# quadcopter.net
KiCad netlist of a schematic drawn in EAGLE
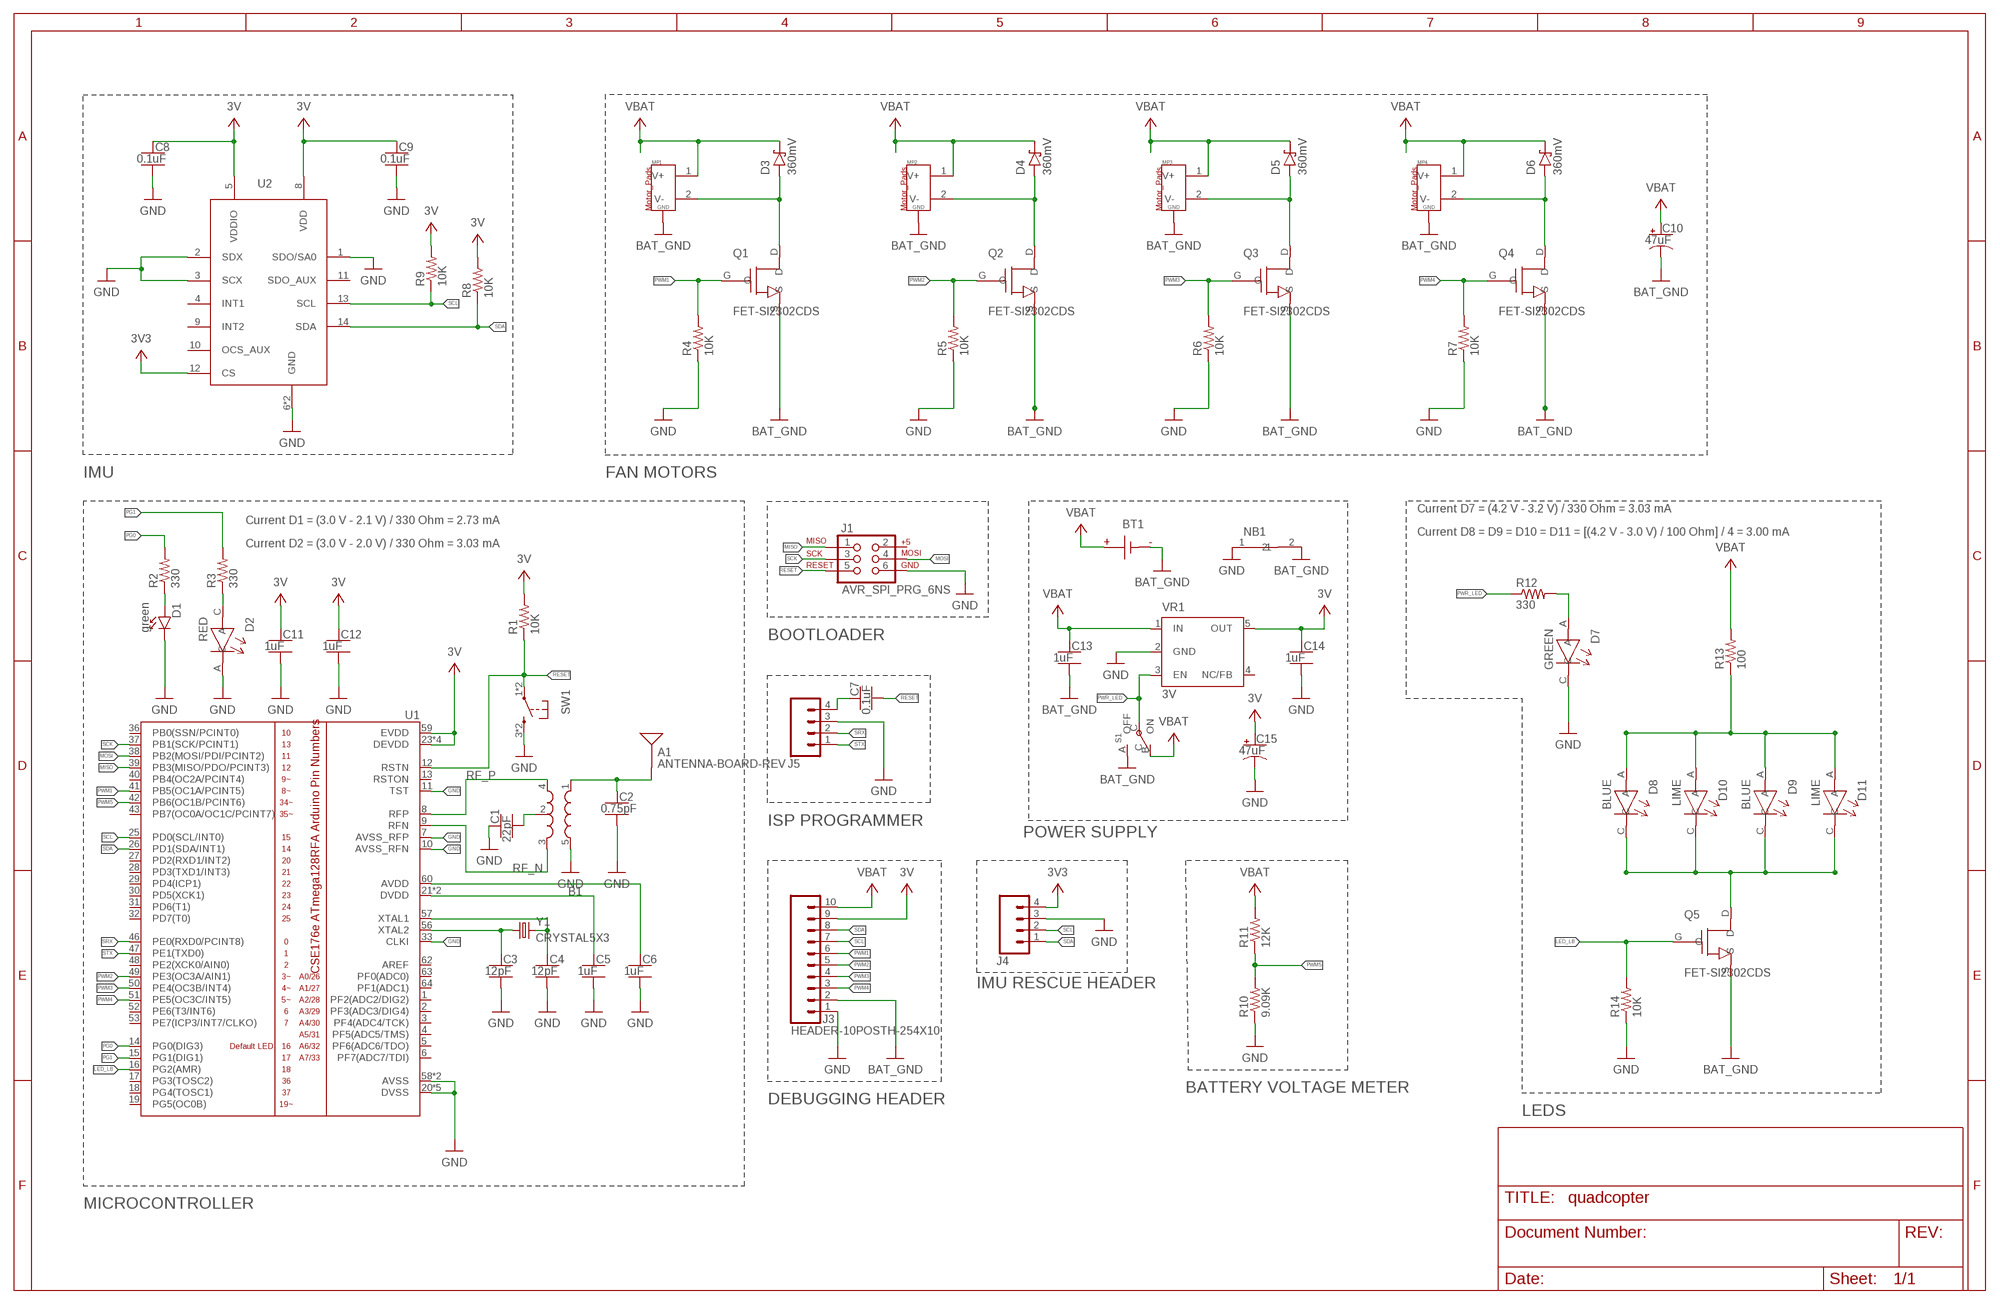
[diagram p0: schematic, sheet 1]

(export (version "E")
  (design (tool "Eeschema 10.0.6"))
  (components
    (comp (ref "A1")
      (value "ANTENNA-BOARD-REV")
      (footprint "eagle-import:ANT_PCB_2.4GHZ_NRF8001_1.6MM_1OZ_REV")
      (fields (field (name "MFR") "NA") (field (name "CREATOR") "Swanson"))
      (libsource (lib "eagle-import") (part "ANTENNA-BOARD-REV"))
    )
    (comp (ref "B1")
      (value "BALUN0805")
      (footprint "eagle-import:BALUN")
      (fields
        (field (name "MFR") "Wurth Electronics Inc.")
        (field (name "MPN") "748421245")
        (field (name "CREATOR") "Swanson")
        (field (name "REVIEWER") "Swanson")
      )
      (libsource (lib "eagle-import") (part "BALUN0805"))
    )
    (comp (ref "BT1")
      (value "BATTERY-SCREW-TERMINAL")
      (footprint "eagle-import:SCREW-TERMINAL-1X2-2.54MM")
      (fields (field (name "CREATOR") "Swanson"))
      (libsource (lib "eagle-import") (part "BATTERY-SCREW-TERMINAL"))
    )
    (comp (ref "C1")
      (value "22pF")
      (footprint "eagle-import:CAPC2012X140_HS")
      (fields
        (field (name "MFR") "Murata Electronics")
        (field (name "MPN") "GRM21A5C2E220JW01D")
        (field (name "CREATOR") "Swanson")
        (field (name "REVIEWER") "Swanson")
      )
      (libsource (lib "eagle-import") (part "CAPACITOR-NP_SMD-2012-0805_CERAMIC-22PF"))
    )
    (comp (ref "C2")
      (value "0.75pF")
      (footprint "eagle-import:CAPC2012X140_HS")
      (fields
        (field (name "MFR") "Murata Electronics")
        (field (name "MPN") "GQM2195C2AR75CB01D")
        (field (name "CREATOR") "Swanson")
        (field (name "REVIEWER") "Swanson")
      )
      (libsource (lib "eagle-import") (part "CAPACITOR-NP_SMD-2012-0805_CERAMIC-0.75PF"))
    )
    (comp (ref "C3")
      (value "12pF")
      (footprint "eagle-import:CAPC2012X140_HS")
      (fields
        (field (name "MFR") "Murata Electronics")
        (field (name "MPN") "GRM21A5C2E120JW01D")
        (field (name "CREATOR") "Swanson")
        (field (name "REVIEWER") "Swanson")
      )
      (libsource (lib "eagle-import") (part "CAPACITOR-NP_SMD-2012-0805_CERAMIC-12PF"))
    )
    (comp (ref "C4")
      (value "12pF")
      (footprint "eagle-import:CAPC2012X140_HS")
      (fields
        (field (name "MFR") "Murata Electronics")
        (field (name "MPN") "GRM21A5C2E120JW01D")
        (field (name "CREATOR") "Swanson")
        (field (name "REVIEWER") "Swanson")
      )
      (libsource (lib "eagle-import") (part "CAPACITOR-NP_SMD-2012-0805_CERAMIC-12PF"))
    )
    (comp (ref "C5")
      (value "1uF")
      (footprint "eagle-import:CAPC2012X140_HS")
      (fields
        (field (name "MFR") "Taiyo Yuden")
        (field (name "MPN") "TMK212B7105KG-T")
        (field (name "CREATOR") "Swanson")
        (field (name "REVIEWER") "Swanson")
      )
      (libsource (lib "eagle-import") (part "CAPACITOR-NP_SMD-2012-0805_CERAMIC-1UF"))
    )
    (comp (ref "C6")
      (value "1uF")
      (footprint "eagle-import:CAPC2012X140_HS")
      (fields
        (field (name "MFR") "Taiyo Yuden")
        (field (name "MPN") "TMK212B7105KG-T")
        (field (name "CREATOR") "Swanson")
        (field (name "REVIEWER") "Swanson")
      )
      (libsource (lib "eagle-import") (part "CAPACITOR-NP_SMD-2012-0805_CERAMIC-1UF"))
    )
    (comp (ref "C7")
      (value "0.1uF")
      (footprint "eagle-import:CAPC2012X140_HS")
      (fields
        (field (name "MFR") "TDK Corporation")
        (field (name "MPN") "C2012X7R2A104K125AA")
        (field (name "CREATOR") "Swanson")
        (field (name "REVIEWER") "Swanson")
      )
      (libsource (lib "eagle-import") (part "CAPACITOR-NP_SMD-2012-0805_CERAMIC-0.1UF"))
    )
    (comp (ref "C8")
      (value "0.1uF")
      (footprint "eagle-import:CAPC2012X140_HS")
      (fields
        (field (name "MFR") "TDK Corporation")
        (field (name "MPN") "C2012X7R2A104K125AA")
        (field (name "CREATOR") "Swanson")
        (field (name "REVIEWER") "Swanson")
      )
      (libsource (lib "eagle-import") (part "CAPACITOR-NP_SMD-2012-0805_CERAMIC-0.1UF"))
    )
    (comp (ref "C9")
      (value "0.1uF")
      (footprint "eagle-import:CAPC2012X140_HS")
      (fields
        (field (name "MFR") "TDK Corporation")
        (field (name "MPN") "C2012X7R2A104K125AA")
        (field (name "CREATOR") "Swanson")
        (field (name "REVIEWER") "Swanson")
      )
      (libsource (lib "eagle-import") (part "CAPACITOR-NP_SMD-2012-0805_CERAMIC-0.1UF"))
    )
    (comp (ref "C10")
      (value "47uF")
      (footprint "eagle-import:CAPMP3216X180")
      (fields
        (field (name "MFR") "AVX Corporation")
        (field (name "MPN") "TAJA476K006SNJV")
        (field (name "CREATOR") "Swanson")
      )
      (libsource (lib "eagle-import") (part "CAPACITOR-POL_47UF-SMD-1206-TAJA"))
    )
    (comp (ref "C11")
      (value "1uF")
      (footprint "eagle-import:CAPC2012X140_HS")
      (fields
        (field (name "MFR") "Taiyo Yuden")
        (field (name "MPN") "TMK212B7105KG-T")
        (field (name "CREATOR") "Swanson")
        (field (name "REVIEWER") "Swanson")
      )
      (libsource (lib "eagle-import") (part "CAPACITOR-NP_SMD-2012-0805_CERAMIC-1UF"))
    )
    (comp (ref "C12")
      (value "1uF")
      (footprint "eagle-import:CAPC2012X140_HS")
      (fields
        (field (name "MFR") "Taiyo Yuden")
        (field (name "MPN") "TMK212B7105KG-T")
        (field (name "CREATOR") "Swanson")
        (field (name "REVIEWER") "Swanson")
      )
      (libsource (lib "eagle-import") (part "CAPACITOR-NP_SMD-2012-0805_CERAMIC-1UF"))
    )
    (comp (ref "C13")
      (value "1uF")
      (footprint "eagle-import:CAPC2012X140_HS")
      (fields
        (field (name "MFR") "Taiyo Yuden")
        (field (name "MPN") "TMK212B7105KG-T")
        (field (name "CREATOR") "Swanson")
        (field (name "REVIEWER") "Swanson")
      )
      (libsource (lib "eagle-import") (part "CAPACITOR-NP_SMD-2012-0805_CERAMIC-1UF"))
    )
    (comp (ref "C14")
      (value "1uF")
      (footprint "eagle-import:CAPC2012X140_HS")
      (fields
        (field (name "MFR") "Taiyo Yuden")
        (field (name "MPN") "TMK212B7105KG-T")
        (field (name "CREATOR") "Swanson")
        (field (name "REVIEWER") "Swanson")
      )
      (libsource (lib "eagle-import") (part "CAPACITOR-NP_SMD-2012-0805_CERAMIC-1UF"))
    )
    (comp (ref "C15")
      (value "47uF")
      (footprint "eagle-import:CAPMP3216X180")
      (fields
        (field (name "MFR") "AVX Corporation")
        (field (name "MPN") "TAJA476K006SNJV")
        (field (name "CREATOR") "Swanson")
      )
      (libsource (lib "eagle-import") (part "CAPACITOR-POL_47UF-SMD-1206-TAJA"))
    )
    (comp (ref "D1")
      (value "green")
      (footprint "eagle-import:LEDSC125X200X120-2_HS")
      (fields
        (field (name "MFR") "Lite-On Inc")
        (field (name "MPN") "LTST-C170GKT")
        (field (name "CREATOR") "Swanson")
        (field (name "REVIEWER") "Swanson")
      )
      (libsource (lib "eagle-import") (part "DIODE-LED_SMD-2012-0805-GREEN"))
    )
    (comp (ref "D2")
      (value "RED")
      (footprint "eagle-import:0805_LED")
      (fields (field (name "CREATOR") "CHRISTOPHER VU"))
      (libsource (lib "eagle-import") (part "LED-RED"))
    )
    (comp (ref "D3")
      (value "360mV")
      (footprint "eagle-import:SODFL3516X96")
      (fields
        (field (name "MFR") "Toshiba Semiconductor and Storage")
        (field (name "MPN") "CRS08(TE85L,Q,M)")
        (field (name "CREATOR") "Swanson")
        (field (name "REVIEWER") "Swanson")
      )
      (libsource (lib "eagle-import") (part "DIODE-SCHOTTKY_-SMD-SOD123"))
    )
    (comp (ref "D4")
      (value "360mV")
      (footprint "eagle-import:SODFL3516X96")
      (fields
        (field (name "MFR") "Toshiba Semiconductor and Storage")
        (field (name "MPN") "CRS08(TE85L,Q,M)")
        (field (name "CREATOR") "Swanson")
        (field (name "REVIEWER") "Swanson")
      )
      (libsource (lib "eagle-import") (part "DIODE-SCHOTTKY_-SMD-SOD123"))
    )
    (comp (ref "D5")
      (value "360mV")
      (footprint "eagle-import:SODFL3516X96")
      (fields
        (field (name "MFR") "Toshiba Semiconductor and Storage")
        (field (name "MPN") "CRS08(TE85L,Q,M)")
        (field (name "CREATOR") "Swanson")
        (field (name "REVIEWER") "Swanson")
      )
      (libsource (lib "eagle-import") (part "DIODE-SCHOTTKY_-SMD-SOD123"))
    )
    (comp (ref "D6")
      (value "360mV")
      (footprint "eagle-import:SODFL3516X96")
      (fields
        (field (name "MFR") "Toshiba Semiconductor and Storage")
        (field (name "MPN") "CRS08(TE85L,Q,M)")
        (field (name "CREATOR") "Swanson")
        (field (name "REVIEWER") "Swanson")
      )
      (libsource (lib "eagle-import") (part "DIODE-SCHOTTKY_-SMD-SOD123"))
    )
    (comp (ref "D7")
      (value "GREEN")
      (footprint "eagle-import:0805_LED")
      (fields (field (name "CREATOR") "CHRISTOPHER VU"))
      (libsource (lib "eagle-import") (part "0805_LED-GREEN"))
    )
    (comp (ref "D8")
      (value "BLUE")
      (footprint "eagle-import:1411_LED")
      (fields (field (name "CREATOR") "CHRISTOPHER VU"))
      (libsource (lib "eagle-import") (part "1411_LED-BLUE"))
    )
    (comp (ref "D9")
      (value "BLUE")
      (footprint "eagle-import:1411_LED")
      (fields (field (name "CREATOR") "CHRISTOPHER VU"))
      (libsource (lib "eagle-import") (part "1411_LED-BLUE"))
    )
    (comp (ref "D10")
      (value "LIME")
      (footprint "eagle-import:1411_LED")
      (fields (field (name "CREATOR") "CHRISTOPHER VU"))
      (libsource (lib "eagle-import") (part "1411_LED-LIME"))
    )
    (comp (ref "D11")
      (value "LIME")
      (footprint "eagle-import:1411_LED")
      (fields (field (name "CREATOR") "CHRISTOPHER VU"))
      (libsource (lib "eagle-import") (part "1411_LED-LIME"))
    )
    (comp (ref "J1")
      (value "AVR_SPI_PRG_6NS")
      (footprint "eagle-import:2X3-NS")
      (fields
        (field (name "MFR") "Amphenol FCI")
        (field (name "MPN") "67997-206HLF")
        (field (name "CREATOR") "Swanson")
        (field (name "REVIEWER") "Swanson")
      )
      (libsource (lib "eagle-import") (part "AVR_SPI_PRG_6NS"))
    )
    (comp (ref "J3")
      (value "HEADER-10POSTH-254X10")
      (footprint "eagle-import:HDRV10W63P254_10X1_2540X254H838_HS")
      (fields
        (field (name "MFR") "Amphenol FCI")
        (field (name "MPN") "68000-110HLF")
        (field (name "CREATOR") "Swanson")
        (field (name "REVIEWER") "Swanson")
      )
      (libsource (lib "eagle-import") (part "HEADER-10POSTH-254X10"))
    )
    (comp (ref "J4")
      (value "HEADER-4POS-0.1IN-FEMALE")
      (footprint "eagle-import:HDRVR4W80P254_1X4_1066X254X850B")
      (fields (field (name "CREATOR") "Swanson"))
      (libsource (lib "eagle-import") (part "HEADER-4POS-0.1IN-FEMALE"))
    )
    (comp (ref "J5")
      (value "HEADER-4POS-0.1IN-FEMALE-SMD-BOTTOM-ENTRY")
      (footprint "eagle-import:HEADER-1X4-BOTTOM-ENTRY")
      (fields
        (field (name "MFR") "TE Connectivity AMP Connectors")
        (field (name "MPN") "1241152-4")
        (field (name "CREATOR") "Swanson")
      )
      (libsource (lib "eagle-import") (part "HEADER-4POS-0.1IN-FEMALE-SMD-BOTTOM-ENTRY"))
    )
    (comp (ref "MP1")
      (value "MOTOR_PADS_GND-MOLEX-SMD")
      (footprint "eagle-import:MOLEX-0532610271")
      (fields
        (field (name "MFR") "Molex")
        (field (name "MPN") "532610271")
        (field (name "CREATOR") "Swanson")
      )
      (libsource (lib "eagle-import") (part "MOTOR_PADS_GND-MOLEX-SMD"))
    )
    (comp (ref "MP2")
      (value "MOTOR_PADS_GND-MOLEX-SMD")
      (footprint "eagle-import:MOLEX-0532610271")
      (fields
        (field (name "MFR") "Molex")
        (field (name "MPN") "532610271")
        (field (name "CREATOR") "Swanson")
      )
      (libsource (lib "eagle-import") (part "MOTOR_PADS_GND-MOLEX-SMD"))
    )
    (comp (ref "MP3")
      (value "MOTOR_PADS_GND-MOLEX-SMD")
      (footprint "eagle-import:MOLEX-0532610271")
      (fields
        (field (name "MFR") "Molex")
        (field (name "MPN") "532610271")
        (field (name "CREATOR") "Swanson")
      )
      (libsource (lib "eagle-import") (part "MOTOR_PADS_GND-MOLEX-SMD"))
    )
    (comp (ref "MP4")
      (value "MOTOR_PADS_GND-MOLEX-SMD")
      (footprint "eagle-import:MOLEX-0532610271")
      (fields
        (field (name "MFR") "Molex")
        (field (name "MPN") "532610271")
        (field (name "CREATOR") "Swanson")
      )
      (libsource (lib "eagle-import") (part "MOTOR_PADS_GND-MOLEX-SMD"))
    )
    (comp (ref "NB1")
      (value "NET-BRIDGE")
      (footprint "eagle-import:NET-BRIDGE")
      (fields (field (name "CREATOR") "DARRYL TAYAG"))
      (libsource (lib "eagle-import") (part "NET-BRIDGE"))
    )
    (comp (ref "Q1")
      (value "FET-SI2302CDS")
      (footprint "eagle-import:SI2302MOSFET")
      (fields (field (name "CREATOR") "CHRISTOPHER VU"))
      (libsource (lib "eagle-import") (part "FET-SI2302CDS"))
    )
    (comp (ref "Q2")
      (value "FET-SI2302CDS")
      (footprint "eagle-import:SI2302MOSFET")
      (fields (field (name "CREATOR") "CHRISTOPHER VU"))
      (libsource (lib "eagle-import") (part "FET-SI2302CDS"))
    )
    (comp (ref "Q3")
      (value "FET-SI2302CDS")
      (footprint "eagle-import:SI2302MOSFET")
      (fields (field (name "CREATOR") "CHRISTOPHER VU"))
      (libsource (lib "eagle-import") (part "FET-SI2302CDS"))
    )
    (comp (ref "Q4")
      (value "FET-SI2302CDS")
      (footprint "eagle-import:SI2302MOSFET")
      (fields (field (name "CREATOR") "CHRISTOPHER VU"))
      (libsource (lib "eagle-import") (part "FET-SI2302CDS"))
    )
    (comp (ref "Q5")
      (value "FET-SI2302CDS")
      (footprint "eagle-import:SI2302MOSFET")
      (fields (field (name "CREATOR") "CHRISTOPHER VU"))
      (libsource (lib "eagle-import") (part "FET-SI2302CDS"))
    )
    (comp (ref "R1")
      (value "10K")
      (footprint "eagle-import:RESC2012X60_HS")
      (fields
        (field (name "MFR") "Yageo")
        (field (name "MPN") "RC0805JR-0710KL")
        (field (name "CREATOR") "Swanson")
        (field (name "REVIEWER") "Swanson")
      )
      (libsource (lib "eagle-import") (part "RESISTOR_SMD-2012-0805-10K"))
    )
    (comp (ref "R2")
      (value "330")
      (footprint "eagle-import:RESC2012X60_HS")
      (fields
        (field (name "MFR") "Yageo")
        (field (name "MPN") "RC0805JR-07330RL")
        (field (name "CREATOR") "Swanson")
        (field (name "REVIEWER") "Swanson")
      )
      (libsource (lib "eagle-import") (part "RESISTOR_SMD-2012-0805-330"))
    )
    (comp (ref "R3")
      (value "330")
      (footprint "eagle-import:RESC2012X60_HS")
      (fields
        (field (name "MFR") "Yageo")
        (field (name "MPN") "RC0805JR-07330RL")
        (field (name "CREATOR") "Swanson")
        (field (name "REVIEWER") "Swanson")
      )
      (libsource (lib "eagle-import") (part "RESISTOR_SMD-2012-0805-330"))
    )
    (comp (ref "R4")
      (value "10K")
      (footprint "eagle-import:RESC2012X60_HS")
      (fields
        (field (name "MFR") "Yageo")
        (field (name "MPN") "RC0805JR-0710KL")
        (field (name "CREATOR") "Swanson")
        (field (name "REVIEWER") "Swanson")
      )
      (libsource (lib "eagle-import") (part "RESISTOR_SMD-2012-0805-10K"))
    )
    (comp (ref "R5")
      (value "10K")
      (footprint "eagle-import:RESC2012X60_HS")
      (fields
        (field (name "MFR") "Yageo")
        (field (name "MPN") "RC0805JR-0710KL")
        (field (name "CREATOR") "Swanson")
        (field (name "REVIEWER") "Swanson")
      )
      (libsource (lib "eagle-import") (part "RESISTOR_SMD-2012-0805-10K"))
    )
    (comp (ref "R6")
      (value "10K")
      (footprint "eagle-import:RESC2012X60_HS")
      (fields
        (field (name "MFR") "Yageo")
        (field (name "MPN") "RC0805JR-0710KL")
        (field (name "CREATOR") "Swanson")
        (field (name "REVIEWER") "Swanson")
      )
      (libsource (lib "eagle-import") (part "RESISTOR_SMD-2012-0805-10K"))
    )
    (comp (ref "R7")
      (value "10K")
      (footprint "eagle-import:RESC2012X60_HS")
      (fields
        (field (name "MFR") "Yageo")
        (field (name "MPN") "RC0805JR-0710KL")
        (field (name "CREATOR") "Swanson")
        (field (name "REVIEWER") "Swanson")
      )
      (libsource (lib "eagle-import") (part "RESISTOR_SMD-2012-0805-10K"))
    )
    (comp (ref "R8")
      (value "10K")
      (footprint "eagle-import:RESC2012X60_HS")
      (fields
        (field (name "MFR") "Yageo")
        (field (name "MPN") "RC0805JR-0710KL")
        (field (name "CREATOR") "Swanson")
        (field (name "REVIEWER") "Swanson")
      )
      (libsource (lib "eagle-import") (part "RESISTOR_SMD-2012-0805-10K"))
    )
    (comp (ref "R9")
      (value "10K")
      (footprint "eagle-import:RESC2012X60_HS")
      (fields
        (field (name "MFR") "Yageo")
        (field (name "MPN") "RC0805JR-0710KL")
        (field (name "CREATOR") "Swanson")
        (field (name "REVIEWER") "Swanson")
      )
      (libsource (lib "eagle-import") (part "RESISTOR_SMD-2012-0805-10K"))
    )
    (comp (ref "R10")
      (value "9.09K")
      (footprint "eagle-import:RESC2012X60_HS")
      (fields (field (name "CREATOR") "Swanson"))
      (libsource (lib "eagle-import") (part "RESISTOR_SMD-2012-0805-9.09K"))
    )
    (comp (ref "R11")
      (value "12K")
      (footprint "eagle-import:RESC2012X60_HS")
      (fields (field (name "CREATOR") "Swanson"))
      (libsource (lib "eagle-import") (part "RESISTOR_SMD-2012-0805-12K"))
    )
    (comp (ref "R12")
      (value "330")
      (footprint "eagle-import:RESC2012X60_HS")
      (fields
        (field (name "MFR") "Yageo")
        (field (name "MPN") "RC0805JR-07330RL")
        (field (name "CREATOR") "Swanson")
        (field (name "REVIEWER") "Swanson")
      )
      (libsource (lib "eagle-import") (part "RESISTOR_SMD-2012-0805-330"))
    )
    (comp (ref "R13")
      (value "100")
      (footprint "eagle-import:RESC2012X60_HS")
      (fields
        (field (name "MFR") "Yageo")
        (field (name "MPN") "RC0805JR-07100RL")
        (field (name "CREATOR") "Swanson")
        (field (name "REVIEWER") "Swanson")
      )
      (libsource (lib "eagle-import") (part "RESISTOR_SMD-2012-0805-100"))
    )
    (comp (ref "R14")
      (value "10K")
      (footprint "eagle-import:RESC2012X60_HS")
      (fields
        (field (name "MFR") "Yageo")
        (field (name "MPN") "RC0805JR-0710KL")
        (field (name "CREATOR") "Swanson")
        (field (name "REVIEWER") "Swanson")
      )
      (libsource (lib "eagle-import") (part "RESISTOR_SMD-2012-0805-10K"))
    )
    (comp (ref "S1")
      (value "POWER-SWITCH-MFS201N-9-Z-SMD-EDGE")
      (footprint "eagle-import:JS102011SAQN")
      (fields
        (field (name "MFR") "C&K")
        (field (name "MPN") "JS102011SAQN")
        (field (name "CREATOR") "Swanson")
      )
      (libsource (lib "eagle-import") (part "POWER-SWITCH-MFS201N-9-Z-SMD-EDGE"))
    )
    (comp (ref "SW1")
      (value "PUSHBUTTON_SMD-VERTICAL-1")
      (footprint "eagle-import:TE_FSM8JSMA_HS")
      (fields
        (field (name "MFR") "TE Connectivity Alcoswitch Switches")
        (field (name "MPN") "FSM4JSMA")
        (field (name "CREATOR") "Swanson")
        (field (name "REVIEWER") "Swanson")
      )
      (libsource (lib "eagle-import") (part "PUSHBUTTON_SMD-VERTICAL-1"))
    )
    (comp (ref "U1")
      (value "ATMEGA128RFA1")
      (footprint "eagle-import:QFN-64")
      (fields
        (field (name "MFR") "Microchip Technology")
        (field (name "MPN") "ATMEGA128RFA1-ZU")
        (field (name "CREATOR") "Swanson")
        (field (name "REVIEWER") "Swanson")
      )
      (libsource (lib "eagle-import") (part "ATMEGA128RFA1"))
    )
    (comp (ref "U2")
      (value "IMU_LSM6DSOX-LSM6DSOXTR")
      (footprint "eagle-import:LSM6DS0XTR")
      (fields (field (name "CREATOR") "CHRISTOPHER VU"))
      (libsource (lib "eagle-import") (part "IMU_LSM6DSOX-LSM6DSOXTR"))
    )
    (comp (ref "VR1")
      (value "3V")
      (footprint "eagle-import:SOT23-DBV")
      (fields
        (field (name "MFR") "Texas Instruments")
        (field (name "MPN") "LP3985IM5X-3.0/NOPB")
        (field (name "CREATOR") "Swanson")
        (field (name "REVIEWER") "Swanson")
      )
      (libsource (lib "eagle-import") (part "TPS73633-DBVT3V"))
    )
    (comp (ref "Y1")
      (value "CRYSTAL5X3")
      (footprint "eagle-import:CRYSTAL-SMD-5X3")
      (fields
        (field (name "MFR") "Abracon LLC")
        (field (name "MPN") "ABM3B-16.000MHZ-B2-T")
        (field (name "CREATOR") "Swanson")
        (field (name "REVIEWER") "Swanson")
      )
      (libsource (lib "eagle-import") (part "CRYSTAL5X3"))
    )
  )
  (nets
    (net (code "1") (name "/RF_N") (class "Default")
      (node (ref "B1") (pin "3") (pinfunction "OUT2_3") (pintype "bidirectional"))
      (node (ref "U1") (pin "9") (pinfunction "RFN_9") (pintype "bidirectional"))
    )
    (net (code "2") (name "/RF_P") (class "Default")
      (node (ref "B1") (pin "4") (pinfunction "OUT1_4") (pintype "bidirectional"))
      (node (ref "U1") (pin "8") (pinfunction "RFP_8") (pintype "bidirectional"))
    )
    (net (code "3") (name "3V") (class "Default")
      (node (ref "C11") (pin "1") (pinfunction "1_1") (pintype "passive"))
      (node (ref "C12") (pin "1") (pinfunction "1_1") (pintype "passive"))
      (node (ref "C14") (pin "1") (pinfunction "1_1") (pintype "passive"))
      (node (ref "C15") (pin "1") (pinfunction "+_1") (pintype "passive"))
      (node (ref "C8") (pin "1") (pinfunction "1_1") (pintype "passive"))
      (node (ref "C9") (pin "1") (pinfunction "1_1") (pintype "passive"))
      (node (ref "J3") (pin "9") (pinfunction "9_9") (pintype "passive"))
      (node (ref "J4") (pin "4") (pinfunction "4_4") (pintype "bidirectional"))
      (node (ref "R1") (pin "2") (pinfunction "2_2") (pintype "passive"))
      (node (ref "R8") (pin "2") (pinfunction "2_2") (pintype "passive"))
      (node (ref "R9") (pin "2") (pinfunction "2_2") (pintype "passive"))
      (node (ref "U1") (pin "23") (pinfunction "DEVDD_23") (pintype "bidirectional"))
      (node (ref "U1") (pin "34") (pinfunction "DEVDD_34") (pintype "bidirectional"))
      (node (ref "U1") (pin "44") (pinfunction "DEVDD_44") (pintype "bidirectional"))
      (node (ref "U1") (pin "54") (pinfunction "DEVDD_54") (pintype "bidirectional"))
      (node (ref "U1") (pin "59") (pinfunction "EVDD_59") (pintype "bidirectional"))
      (node (ref "U2") (pin "12") (pinfunction "CS_12") (pintype "bidirectional"))
      (node (ref "U2") (pin "5") (pinfunction "VDDIO_5") (pintype "bidirectional"))
      (node (ref "U2") (pin "8") (pinfunction "VDD_8") (pintype "bidirectional"))
      (node (ref "VR1") (pin "5") (pinfunction "OUT_5") (pintype "passive"))
    )
    (net (code "4") (name "BAT_GND") (class "Default")
      (node (ref "BT1") (pin "1") (pinfunction "N_1") (pintype "bidirectional"))
      (node (ref "C10") (pin "2") (pinfunction "-_2") (pintype "passive"))
      (node (ref "C13") (pin "2") (pinfunction "2_2") (pintype "passive"))
      (node (ref "J3") (pin "2") (pinfunction "2_2") (pintype "passive"))
      (node (ref "MP1") (pin "G1") (pinfunction "GND_G1") (pintype "bidirectional"))
      (node (ref "MP1") (pin "G2") (pinfunction "GND_G2") (pintype "bidirectional"))
      (node (ref "MP2") (pin "G1") (pinfunction "GND_G1") (pintype "bidirectional"))
      (node (ref "MP2") (pin "G2") (pinfunction "GND_G2") (pintype "bidirectional"))
      (node (ref "MP3") (pin "G1") (pinfunction "GND_G1") (pintype "bidirectional"))
      (node (ref "MP3") (pin "G2") (pinfunction "GND_G2") (pintype "bidirectional"))
      (node (ref "MP4") (pin "G1") (pinfunction "GND_G1") (pintype "bidirectional"))
      (node (ref "MP4") (pin "G2") (pinfunction "GND_G2") (pintype "bidirectional"))
      (node (ref "NB1") (pin "2") (pinfunction "2_2") (pintype "bidirectional"))
      (node (ref "Q1") (pin "S") (pinfunction "S_S") (pintype "bidirectional"))
      (node (ref "Q2") (pin "S") (pinfunction "S_S") (pintype "bidirectional"))
      (node (ref "Q3") (pin "S") (pinfunction "S_S") (pintype "bidirectional"))
      (node (ref "Q4") (pin "S") (pinfunction "S_S") (pintype "bidirectional"))
      (node (ref "Q5") (pin "S") (pinfunction "S_S") (pintype "bidirectional"))
      (node (ref "S1") (pin "A") (pinfunction "OFF_A") (pintype "bidirectional"))
    )
    (net (code "5") (name "GND") (class "Default")
      (node (ref "B1") (pin "5") (pinfunction "GND_5") (pintype "bidirectional"))
      (node (ref "C1") (pin "1") (pinfunction "1_1") (pintype "passive"))
      (node (ref "C11") (pin "2") (pinfunction "2_2") (pintype "passive"))
      (node (ref "C12") (pin "2") (pinfunction "2_2") (pintype "passive"))
      (node (ref "C14") (pin "2") (pinfunction "2_2") (pintype "passive"))
      (node (ref "C15") (pin "2") (pinfunction "-_2") (pintype "passive"))
      (node (ref "C2") (pin "2") (pinfunction "2_2") (pintype "passive"))
      (node (ref "C3") (pin "2") (pinfunction "2_2") (pintype "passive"))
      (node (ref "C4") (pin "2") (pinfunction "2_2") (pintype "passive"))
      (node (ref "C5") (pin "2") (pinfunction "2_2") (pintype "passive"))
      (node (ref "C6") (pin "2") (pinfunction "2_2") (pintype "passive"))
      (node (ref "C8") (pin "2") (pinfunction "2_2") (pintype "passive"))
      (node (ref "C9") (pin "2") (pinfunction "2_2") (pintype "passive"))
      (node (ref "D1") (pin "C") (pinfunction "C_C") (pintype "passive"))
      (node (ref "D2") (pin "A") (pinfunction "C_A") (pintype "bidirectional"))
      (node (ref "D7") (pin "C") (pinfunction "C_C") (pintype "bidirectional"))
      (node (ref "J1") (pin "6") (pinfunction "6_6") (pintype "passive"))
      (node (ref "J3") (pin "1") (pinfunction "1_1") (pintype "passive"))
      (node (ref "J4") (pin "3") (pinfunction "3_3") (pintype "bidirectional"))
      (node (ref "J5") (pin "3") (pinfunction "3_3") (pintype "bidirectional"))
      (node (ref "NB1") (pin "1") (pinfunction "1_1") (pintype "bidirectional"))
      (node (ref "R10") (pin "1") (pinfunction "1_1") (pintype "passive"))
      (node (ref "R14") (pin "1") (pinfunction "1_1") (pintype "passive"))
      (node (ref "R4") (pin "1") (pinfunction "1_1") (pintype "passive"))
      (node (ref "R5") (pin "1") (pinfunction "1_1") (pintype "passive"))
      (node (ref "R6") (pin "1") (pinfunction "1_1") (pintype "passive"))
      (node (ref "R7") (pin "1") (pinfunction "1_1") (pintype "passive"))
      (node (ref "SW1") (pin "3") (pinfunction "2_3") (pintype "passive"))
      (node (ref "SW1") (pin "4") (pinfunction "2_4") (pintype "passive"))
      (node (ref "U1") (pin "10") (pinfunction "AVSS_RFN_10") (pintype "bidirectional"))
      (node (ref "U1") (pin "11") (pinfunction "TST_11") (pintype "bidirectional"))
      (node (ref "U1") (pin "20") (pinfunction "DVSS_20") (pintype "bidirectional"))
      (node (ref "U1") (pin "24") (pinfunction "DVSS_24") (pintype "bidirectional"))
      (node (ref "U1") (pin "33") (pinfunction "CLKI_33") (pintype "bidirectional"))
      (node (ref "U1") (pin "35") (pinfunction "DVSS_35") (pintype "bidirectional"))
      (node (ref "U1") (pin "45") (pinfunction "DVSS_45") (pintype "bidirectional"))
      (node (ref "U1") (pin "55") (pinfunction "DVSS_55") (pintype "bidirectional"))
      (node (ref "U1") (pin "58") (pinfunction "AVSS_58") (pintype "bidirectional"))
      (node (ref "U1") (pin "61") (pinfunction "AVSS_61") (pintype "bidirectional"))
      (node (ref "U1") (pin "7") (pinfunction "AVSS_RFP_7") (pintype "bidirectional"))
      (node (ref "U2") (pin "1") (pinfunction "SDO/SA0_1") (pintype "bidirectional"))
      (node (ref "U2") (pin "2") (pinfunction "SDX_2") (pintype "bidirectional"))
      (node (ref "U2") (pin "3") (pinfunction "SCX_3") (pintype "bidirectional"))
      (node (ref "U2") (pin "6") (pinfunction "GND_6") (pintype "bidirectional"))
      (node (ref "U2") (pin "7") (pinfunction "GND_7") (pintype "bidirectional"))
      (node (ref "VR1") (pin "2") (pinfunction "GND_2") (pintype "input"))
    )
    (net (code "6") (name "LED_LB") (class "Default")
      (node (ref "Q5") (pin "G") (pinfunction "G_G") (pintype "bidirectional"))
      (node (ref "R14") (pin "2") (pinfunction "2_2") (pintype "passive"))
      (node (ref "U1") (pin "16") (pinfunction "PG2(AMR)_16") (pintype "bidirectional"))
    )
    (net (code "7") (name "MISO") (class "Default")
      (node (ref "J1") (pin "1") (pinfunction "1_1") (pintype "passive"))
      (node (ref "U1") (pin "39") (pinfunction "PB3(MISO/PDO/PCINT3)_39") (pintype "bidirectional"))
    )
    (net (code "8") (name "MOSI") (class "Default")
      (node (ref "J1") (pin "4") (pinfunction "4_4") (pintype "passive"))
      (node (ref "U1") (pin "38") (pinfunction "PB2(MOSI/PDI/PCINT2)_38") (pintype "bidirectional"))
    )
    (net (code "9") (name "Net-(A1-SIGNAL)") (class "Default")
      (node (ref "A1") (pin "FEED") (pinfunction "SIGNAL_FEED") (pintype "bidirectional"))
      (node (ref "B1") (pin "1") (pinfunction "IN_1") (pintype "bidirectional"))
      (node (ref "C2") (pin "1") (pinfunction "1_1") (pintype "passive"))
    )
    (net (code "10") (name "Net-(B1-GND-Pad2)") (class "Default")
      (node (ref "B1") (pin "2") (pinfunction "GND_2") (pintype "bidirectional"))
      (node (ref "C1") (pin "2") (pinfunction "2_2") (pintype "passive"))
    )
    (net (code "11") (name "Net-(C5-Pad1)") (class "Default")
      (node (ref "C5") (pin "1") (pinfunction "1_1") (pintype "passive"))
      (node (ref "U1") (pin "21") (pinfunction "DVDD_21") (pintype "bidirectional"))
      (node (ref "U1") (pin "22") (pinfunction "DVDD_22") (pintype "bidirectional"))
    )
    (net (code "12") (name "Net-(C7-Pad1)") (class "Default")
      (node (ref "C7") (pin "1") (pinfunction "1_1") (pintype "passive"))
      (node (ref "J5") (pin "4") (pinfunction "4_4") (pintype "bidirectional"))
    )
    (net (code "13") (name "Net-(D1-PadA)") (class "Default")
      (node (ref "D1") (pin "A") (pinfunction "A_A") (pintype "passive"))
      (node (ref "R2") (pin "1") (pinfunction "1_1") (pintype "passive"))
    )
    (net (code "14") (name "Net-(D2-A)") (class "Default")
      (node (ref "D2") (pin "C") (pinfunction "A_C") (pintype "bidirectional"))
      (node (ref "R3") (pin "1") (pinfunction "1_1") (pintype "passive"))
    )
    (net (code "15") (name "Net-(D3-A)") (class "Default")
      (node (ref "D3") (pin "2") (pinfunction "A_2") (pintype "passive"))
      (node (ref "MP1") (pin "2") (pinfunction "V-_2") (pintype "bidirectional"))
      (node (ref "Q1") (pin "D") (pinfunction "D_D") (pintype "bidirectional"))
    )
    (net (code "16") (name "Net-(D4-A)") (class "Default")
      (node (ref "D4") (pin "2") (pinfunction "A_2") (pintype "passive"))
      (node (ref "MP2") (pin "2") (pinfunction "V-_2") (pintype "bidirectional"))
      (node (ref "Q2") (pin "D") (pinfunction "D_D") (pintype "bidirectional"))
    )
    (net (code "17") (name "Net-(D5-A)") (class "Default")
      (node (ref "D5") (pin "2") (pinfunction "A_2") (pintype "passive"))
      (node (ref "MP3") (pin "2") (pinfunction "V-_2") (pintype "bidirectional"))
      (node (ref "Q3") (pin "D") (pinfunction "D_D") (pintype "bidirectional"))
    )
    (net (code "18") (name "Net-(D6-A)") (class "Default")
      (node (ref "D6") (pin "2") (pinfunction "A_2") (pintype "passive"))
      (node (ref "MP4") (pin "2") (pinfunction "V-_2") (pintype "bidirectional"))
      (node (ref "Q4") (pin "D") (pinfunction "D_D") (pintype "bidirectional"))
    )
    (net (code "19") (name "Net-(D7-PadA)") (class "Default")
      (node (ref "D7") (pin "A") (pinfunction "A_A") (pintype "bidirectional"))
      (node (ref "R12") (pin "2") (pinfunction "2_2") (pintype "passive"))
    )
    (net (code "20") (name "Net-(D10-PadA)") (class "Default")
      (node (ref "D10") (pin "A") (pinfunction "A_A") (pintype "bidirectional"))
      (node (ref "D11") (pin "A") (pinfunction "A_A") (pintype "bidirectional"))
      (node (ref "D8") (pin "A") (pinfunction "A_A") (pintype "bidirectional"))
      (node (ref "D9") (pin "A") (pinfunction "A_A") (pintype "bidirectional"))
      (node (ref "R13") (pin "1") (pinfunction "1_1") (pintype "passive"))
    )
    (net (code "21") (name "Net-(D10-PadC)") (class "Default")
      (node (ref "D10") (pin "C") (pinfunction "C_C") (pintype "bidirectional"))
      (node (ref "D11") (pin "C") (pinfunction "C_C") (pintype "bidirectional"))
      (node (ref "D8") (pin "C") (pinfunction "C_C") (pintype "bidirectional"))
      (node (ref "D9") (pin "C") (pinfunction "C_C") (pintype "bidirectional"))
      (node (ref "Q5") (pin "D") (pinfunction "D_D") (pintype "bidirectional"))
    )
    (net (code "22") (name "Net-(U1-AVDD)") (class "Default")
      (node (ref "C6") (pin "1") (pinfunction "1_1") (pintype "passive"))
      (node (ref "U1") (pin "60") (pinfunction "AVDD_60") (pintype "bidirectional"))
    )
    (net (code "23") (name "Net-(U1-XTAL1)") (class "Default")
      (node (ref "C4") (pin "1") (pinfunction "1_1") (pintype "passive"))
      (node (ref "U1") (pin "57") (pinfunction "XTAL1_57") (pintype "bidirectional"))
      (node (ref "Y1") (pin "3") (pinfunction "2_3") (pintype "passive"))
    )
    (net (code "24") (name "Net-(U1-XTAL2)") (class "Default")
      (node (ref "C3") (pin "1") (pinfunction "1_1") (pintype "passive"))
      (node (ref "U1") (pin "56") (pinfunction "XTAL2_56") (pintype "bidirectional"))
      (node (ref "Y1") (pin "1") (pinfunction "1_1") (pintype "passive"))
    )
    (net (code "25") (name "PG0") (class "Default")
      (node (ref "R2") (pin "2") (pinfunction "2_2") (pintype "passive"))
      (node (ref "U1") (pin "14") (pinfunction "PG0(DIG3)_14") (pintype "bidirectional"))
    )
    (net (code "26") (name "PG1") (class "Default")
      (node (ref "R3") (pin "2") (pinfunction "2_2") (pintype "passive"))
      (node (ref "U1") (pin "15") (pinfunction "PG1(DIG1)_15") (pintype "bidirectional"))
    )
    (net (code "27") (name "PWM1") (class "Default")
      (node (ref "J3") (pin "6") (pinfunction "6_6") (pintype "passive"))
      (node (ref "Q1") (pin "G") (pinfunction "G_G") (pintype "bidirectional"))
      (node (ref "R4") (pin "2") (pinfunction "2_2") (pintype "passive"))
      (node (ref "U1") (pin "41") (pinfunction "PB5(OC1A/PCINT5)_41") (pintype "bidirectional"))
    )
    (net (code "28") (name "PWM2") (class "Default")
      (node (ref "J3") (pin "5") (pinfunction "5_5") (pintype "passive"))
      (node (ref "Q2") (pin "G") (pinfunction "G_G") (pintype "bidirectional"))
      (node (ref "R5") (pin "2") (pinfunction "2_2") (pintype "passive"))
      (node (ref "U1") (pin "49") (pinfunction "PE3(OC3A/AIN1)_49") (pintype "bidirectional"))
    )
    (net (code "29") (name "PWM3") (class "Default")
      (node (ref "J3") (pin "4") (pinfunction "4_4") (pintype "passive"))
      (node (ref "Q3") (pin "G") (pinfunction "G_G") (pintype "bidirectional"))
      (node (ref "R6") (pin "2") (pinfunction "2_2") (pintype "passive"))
      (node (ref "U1") (pin "50") (pinfunction "PE4(OC3B/INT4)_50") (pintype "bidirectional"))
    )
    (net (code "30") (name "PWM4") (class "Default")
      (node (ref "J3") (pin "3") (pinfunction "3_3") (pintype "passive"))
      (node (ref "Q4") (pin "G") (pinfunction "G_G") (pintype "bidirectional"))
      (node (ref "R7") (pin "2") (pinfunction "2_2") (pintype "passive"))
      (node (ref "U1") (pin "51") (pinfunction "PE5(OC3C/INT5)_51") (pintype "bidirectional"))
    )
    (net (code "31") (name "PWM5") (class "Default")
      (node (ref "R10") (pin "2") (pinfunction "2_2") (pintype "passive"))
      (node (ref "R11") (pin "1") (pinfunction "1_1") (pintype "passive"))
      (node (ref "U1") (pin "42") (pinfunction "PB6(OC1B/PCINT6)_42") (pintype "bidirectional"))
    )
    (net (code "32") (name "PWR_LED") (class "Default")
      (node (ref "R12") (pin "1") (pinfunction "1_1") (pintype "passive"))
      (node (ref "S1") (pin "C") (pinfunction "C_C") (pintype "bidirectional"))
      (node (ref "VR1") (pin "3") (pinfunction "EN_3") (pintype "input"))
    )
    (net (code "33") (name "RESET") (class "Default")
      (node (ref "C7") (pin "2") (pinfunction "2_2") (pintype "passive"))
      (node (ref "J1") (pin "5") (pinfunction "5_5") (pintype "passive"))
      (node (ref "R1") (pin "1") (pinfunction "1_1") (pintype "passive"))
      (node (ref "SW1") (pin "1") (pinfunction "1_1") (pintype "passive"))
      (node (ref "SW1") (pin "2") (pinfunction "1_2") (pintype "passive"))
      (node (ref "U1") (pin "12") (pinfunction "RSTN_12") (pintype "bidirectional"))
    )
    (net (code "34") (name "SCK") (class "Default")
      (node (ref "J1") (pin "3") (pinfunction "3_3") (pintype "passive"))
      (node (ref "U1") (pin "37") (pinfunction "PB1(SCK/PCINT1)_37") (pintype "bidirectional"))
    )
    (net (code "35") (name "SCL") (class "Default")
      (node (ref "J3") (pin "7") (pinfunction "7_7") (pintype "passive"))
      (node (ref "J4") (pin "2") (pinfunction "2_2") (pintype "bidirectional"))
      (node (ref "R9") (pin "1") (pinfunction "1_1") (pintype "passive"))
      (node (ref "U1") (pin "25") (pinfunction "PD0(SCL/INT0)_25") (pintype "bidirectional"))
      (node (ref "U2") (pin "13") (pinfunction "SCL_13") (pintype "bidirectional"))
    )
    (net (code "36") (name "SDA") (class "Default")
      (node (ref "J3") (pin "8") (pinfunction "8_8") (pintype "passive"))
      (node (ref "J4") (pin "1") (pinfunction "1_1") (pintype "bidirectional"))
      (node (ref "R8") (pin "1") (pinfunction "1_1") (pintype "passive"))
      (node (ref "U1") (pin "26") (pinfunction "PD1(SDA/INT1)_26") (pintype "bidirectional"))
      (node (ref "U2") (pin "14") (pinfunction "SDA_14") (pintype "bidirectional"))
    )
    (net (code "37") (name "SRX") (class "Default")
      (node (ref "J5") (pin "2") (pinfunction "2_2") (pintype "bidirectional"))
      (node (ref "U1") (pin "46") (pinfunction "PE0(RXD0/PCINT8)_46") (pintype "bidirectional"))
    )
    (net (code "38") (name "STX") (class "Default")
      (node (ref "J5") (pin "1") (pinfunction "1_1") (pintype "bidirectional"))
      (node (ref "U1") (pin "47") (pinfunction "PE1(TXD0)_47") (pintype "bidirectional"))
    )
    (net (code "39") (name "VBAT") (class "Default")
      (node (ref "BT1") (pin "2") (pinfunction "P_2") (pintype "bidirectional"))
      (node (ref "C10") (pin "1") (pinfunction "+_1") (pintype "passive"))
      (node (ref "C13") (pin "1") (pinfunction "1_1") (pintype "passive"))
      (node (ref "D3") (pin "1") (pinfunction "C_1") (pintype "passive"))
      (node (ref "D4") (pin "1") (pinfunction "C_1") (pintype "passive"))
      (node (ref "D5") (pin "1") (pinfunction "C_1") (pintype "passive"))
      (node (ref "D6") (pin "1") (pinfunction "C_1") (pintype "passive"))
      (node (ref "J3") (pin "10") (pinfunction "10_10") (pintype "passive"))
      (node (ref "MP1") (pin "1") (pinfunction "V+_1") (pintype "bidirectional"))
      (node (ref "MP2") (pin "1") (pinfunction "V+_1") (pintype "bidirectional"))
      (node (ref "MP3") (pin "1") (pinfunction "V+_1") (pintype "bidirectional"))
      (node (ref "MP4") (pin "1") (pinfunction "V+_1") (pintype "bidirectional"))
      (node (ref "R11") (pin "2") (pinfunction "2_2") (pintype "passive"))
      (node (ref "R13") (pin "2") (pinfunction "2_2") (pintype "passive"))
      (node (ref "S1") (pin "B") (pinfunction "ON_B") (pintype "bidirectional"))
      (node (ref "VR1") (pin "1") (pinfunction "IN_1") (pintype "input"))
    )
    (net (code "40") (name "unconnected-(J1-Pad2)") (class "Default")
      (node (ref "J1") (pin "2") (pinfunction "2_2") (pintype "passive"))
    )
    (net (code "41") (name "unconnected-(U1-AREF-Pad62)") (class "Default")
      (node (ref "U1") (pin "62") (pinfunction "AREF_62") (pintype "bidirectional"))
    )
    (net (code "42") (name "unconnected-(U1-PB0(SSN{slash}PCINT0)-Pad36)") (class "Default")
      (node (ref "U1") (pin "36") (pinfunction "PB0(SSN/PCINT0)_36") (pintype "bidirectional"))
    )
    (net (code "43") (name "unconnected-(U1-PB4(OC2A{slash}PCINT4)-Pad40)") (class "Default")
      (node (ref "U1") (pin "40") (pinfunction "PB4(OC2A/PCINT4)_40") (pintype "bidirectional"))
    )
    (net (code "44") (name "unconnected-(U1-PB7(OC0A{slash}OC1C{slash}PCINT7)-Pad43)") (class "Default")
      (node (ref "U1") (pin "43") (pinfunction "PB7(OC0A/OC1C/PCINT7)_43") (pintype "bidirectional"))
    )
    (net (code "45") (name "unconnected-(U1-PD2(RXD1{slash}INT2)-Pad27)") (class "Default")
      (node (ref "U1") (pin "27") (pinfunction "PD2(RXD1/INT2)_27") (pintype "bidirectional"))
    )
    (net (code "46") (name "unconnected-(U1-PD3(TXD1{slash}INT3)-Pad28)") (class "Default")
      (node (ref "U1") (pin "28") (pinfunction "PD3(TXD1/INT3)_28") (pintype "bidirectional"))
    )
    (net (code "47") (name "unconnected-(U1-PD4(ICP1)-Pad29)") (class "Default")
      (node (ref "U1") (pin "29") (pinfunction "PD4(ICP1)_29") (pintype "bidirectional"))
    )
    (net (code "48") (name "unconnected-(U1-PD5(XCK1)-Pad30)") (class "Default")
      (node (ref "U1") (pin "30") (pinfunction "PD5(XCK1)_30") (pintype "bidirectional"))
    )
    (net (code "49") (name "unconnected-(U1-PD6(T1)-Pad31)") (class "Default")
      (node (ref "U1") (pin "31") (pinfunction "PD6(T1)_31") (pintype "bidirectional"))
    )
    (net (code "50") (name "unconnected-(U1-PD7(T0)-Pad32)") (class "Default")
      (node (ref "U1") (pin "32") (pinfunction "PD7(T0)_32") (pintype "bidirectional"))
    )
    (net (code "51") (name "unconnected-(U1-PE2(XCK0{slash}AIN0)-Pad48)") (class "Default")
      (node (ref "U1") (pin "48") (pinfunction "PE2(XCK0/AIN0)_48") (pintype "bidirectional"))
    )
    (net (code "52") (name "unconnected-(U1-PE6(T3{slash}INT6)-Pad52)") (class "Default")
      (node (ref "U1") (pin "52") (pinfunction "PE6(T3/INT6)_52") (pintype "bidirectional"))
    )
    (net (code "53") (name "unconnected-(U1-PE7(ICP3{slash}INT7{slash}CLKO)-Pad53)") (class "Default")
      (node (ref "U1") (pin "53") (pinfunction "PE7(ICP3/INT7/CLKO)_53") (pintype "bidirectional"))
    )
    (net (code "54") (name "unconnected-(U1-PF0(ADC0)-Pad63)") (class "Default")
      (node (ref "U1") (pin "63") (pinfunction "PF0(ADC0)_63") (pintype "bidirectional"))
    )
    (net (code "55") (name "unconnected-(U1-PF1(ADC1)-Pad64)") (class "Default")
      (node (ref "U1") (pin "64") (pinfunction "PF1(ADC1)_64") (pintype "bidirectional"))
    )
    (net (code "56") (name "unconnected-(U1-PF2(ADC2{slash}DIG2)-Pad1)") (class "Default")
      (node (ref "U1") (pin "1") (pinfunction "PF2(ADC2/DIG2)_1") (pintype "bidirectional"))
    )
    (net (code "57") (name "unconnected-(U1-PF3(ADC3{slash}DIG4)-Pad2)") (class "Default")
      (node (ref "U1") (pin "2") (pinfunction "PF3(ADC3/DIG4)_2") (pintype "bidirectional"))
    )
    (net (code "58") (name "unconnected-(U1-PF4(ADC4{slash}TCK)-Pad3)") (class "Default")
      (node (ref "U1") (pin "3") (pinfunction "PF4(ADC4/TCK)_3") (pintype "bidirectional"))
    )
    (net (code "59") (name "unconnected-(U1-PF5(ADC5{slash}TMS)-Pad4)") (class "Default")
      (node (ref "U1") (pin "4") (pinfunction "PF5(ADC5/TMS)_4") (pintype "bidirectional"))
    )
    (net (code "60") (name "unconnected-(U1-PF6(ADC6{slash}TDO)-Pad5)") (class "Default")
      (node (ref "U1") (pin "5") (pinfunction "PF6(ADC6/TDO)_5") (pintype "bidirectional"))
    )
    (net (code "61") (name "unconnected-(U1-PF7(ADC7{slash}TDI)-Pad6)") (class "Default")
      (node (ref "U1") (pin "6") (pinfunction "PF7(ADC7/TDI)_6") (pintype "bidirectional"))
    )
    (net (code "62") (name "unconnected-(U1-PG3(TOSC2)-Pad17)") (class "Default")
      (node (ref "U1") (pin "17") (pinfunction "PG3(TOSC2)_17") (pintype "bidirectional"))
    )
    (net (code "63") (name "unconnected-(U1-PG4(TOSC1)-Pad18)") (class "Default")
      (node (ref "U1") (pin "18") (pinfunction "PG4(TOSC1)_18") (pintype "bidirectional"))
    )
    (net (code "64") (name "unconnected-(U1-PG5(OC0B)-Pad19)") (class "Default")
      (node (ref "U1") (pin "19") (pinfunction "PG5(OC0B)_19") (pintype "bidirectional"))
    )
    (net (code "65") (name "unconnected-(U1-RSTON-Pad13)") (class "Default")
      (node (ref "U1") (pin "13") (pinfunction "RSTON_13") (pintype "bidirectional"))
    )
    (net (code "66") (name "unconnected-(U2-INT1-Pad4)") (class "Default")
      (node (ref "U2") (pin "4") (pinfunction "INT1_4") (pintype "bidirectional"))
    )
    (net (code "67") (name "unconnected-(U2-INT2-Pad9)") (class "Default")
      (node (ref "U2") (pin "9") (pinfunction "INT2_9") (pintype "bidirectional"))
    )
    (net (code "68") (name "unconnected-(U2-OCS_AUX-Pad10)") (class "Default")
      (node (ref "U2") (pin "10") (pinfunction "OCS_AUX_10") (pintype "bidirectional"))
    )
    (net (code "69") (name "unconnected-(U2-SDO_AUX-Pad11)") (class "Default")
      (node (ref "U2") (pin "11") (pinfunction "SDO_AUX_11") (pintype "bidirectional"))
    )
    (net (code "70") (name "unconnected-(VR1-NC{slash}FB-Pad4)") (class "Default")
      (node (ref "VR1") (pin "4") (pinfunction "NC/FB_4") (pintype "passive"))
    )
  )
)
